# record_revf.net
KiCad netlist of a schematic drawn in EAGLE
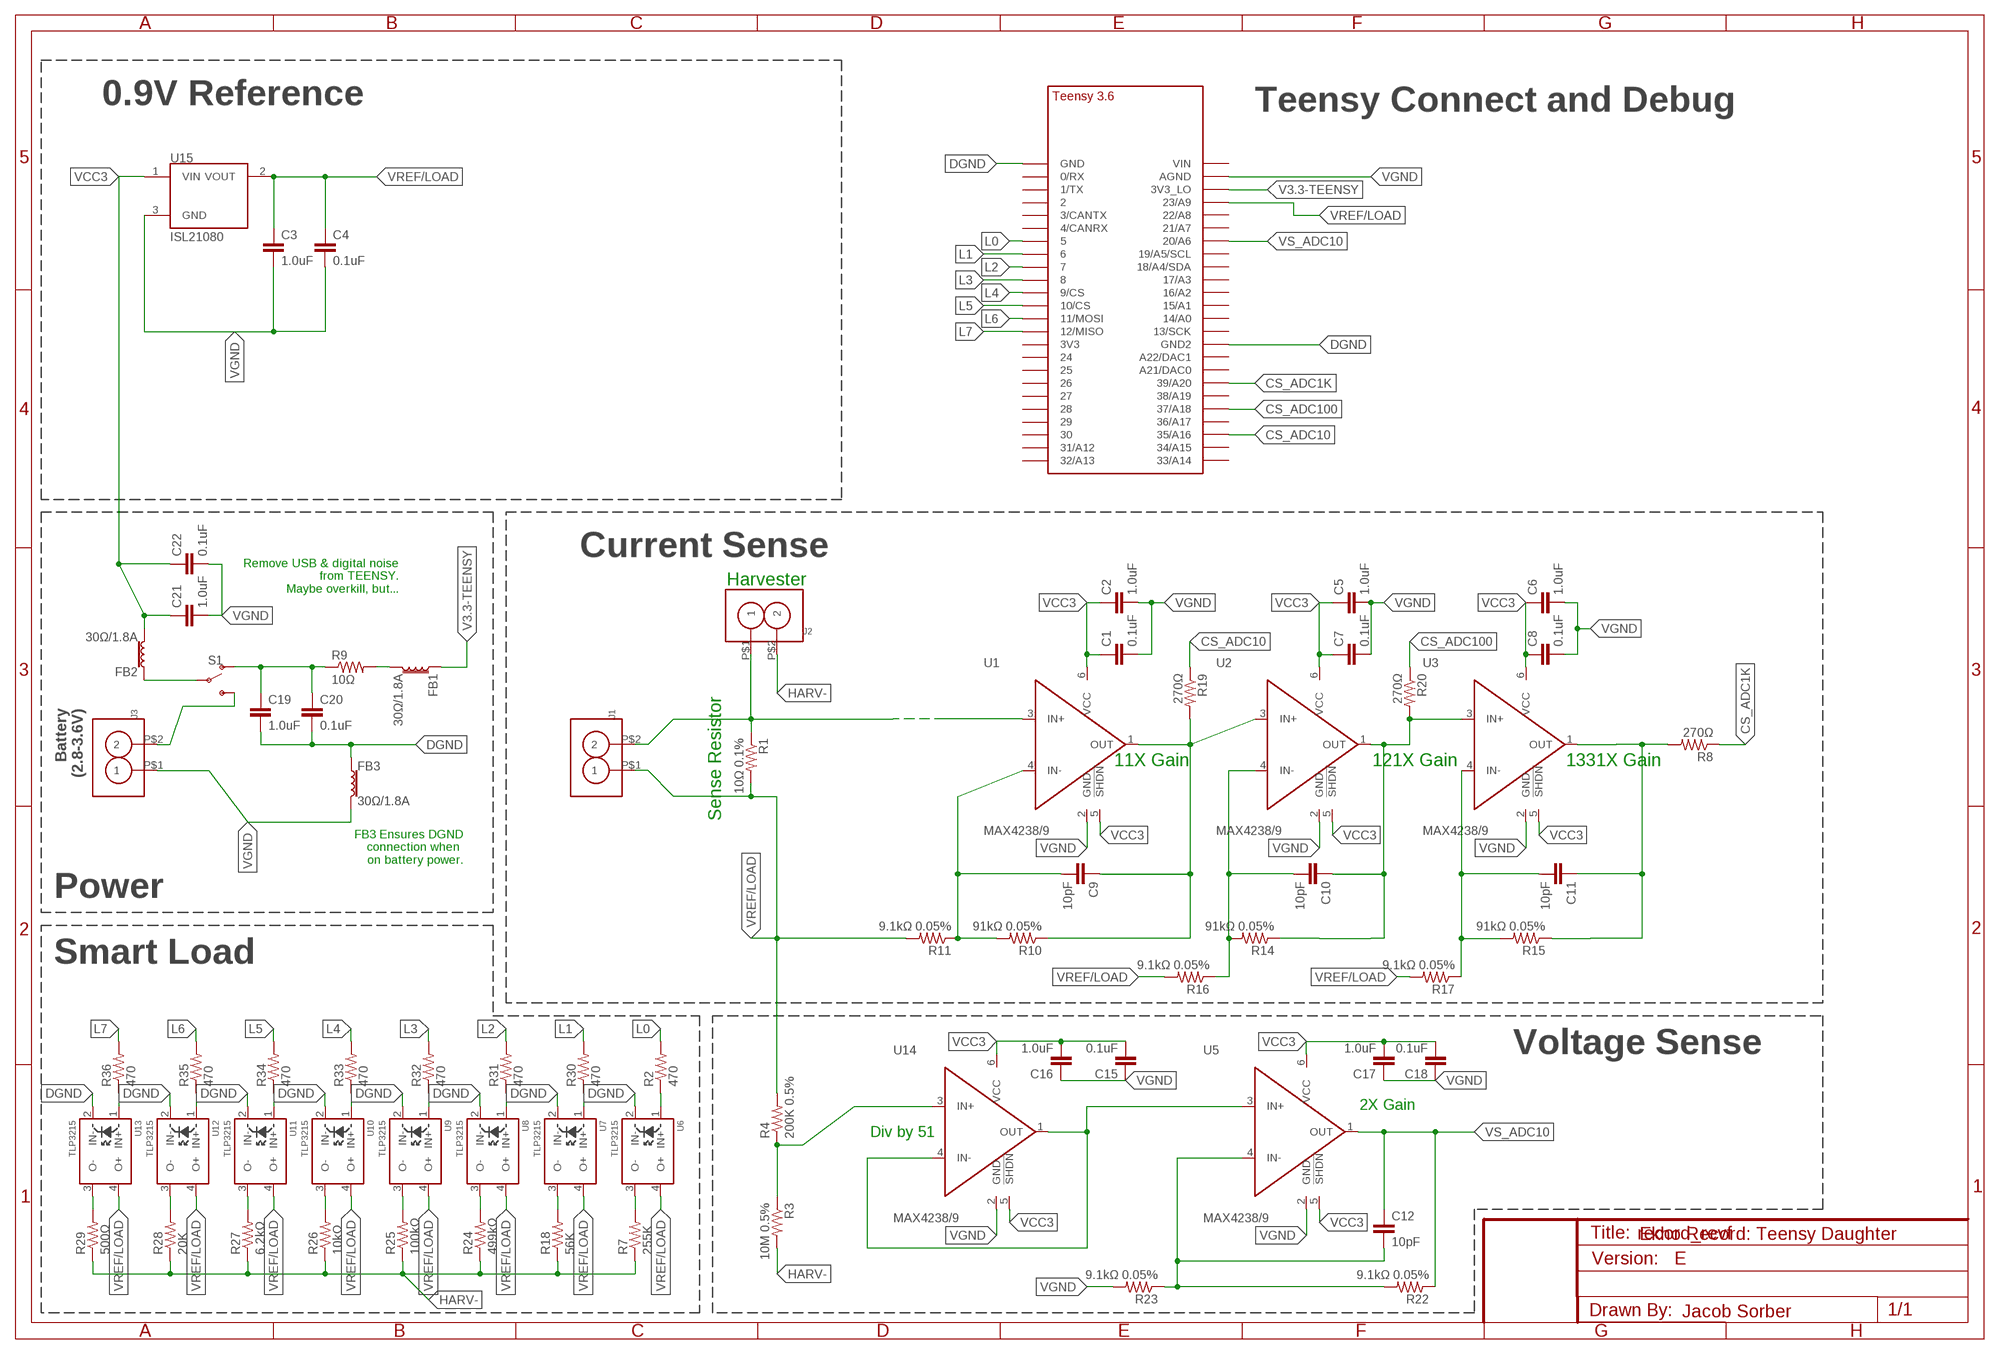
[diagram p0: schematic, sheet 1]

(export (version "E")
  (design (tool "Eeschema 10.0.6"))
  (components
    (comp (ref "C1")
      (value "0.1uF")
      (footprint "eagle-import:0603")
      (libsource (lib "eagle-import") (part "C-EU0603"))
    )
    (comp (ref "C2")
      (value "1.0uF")
      (footprint "eagle-import:0603")
      (libsource (lib "eagle-import") (part "C-EU0603"))
    )
    (comp (ref "C3")
      (value "1.0uF")
      (footprint "eagle-import:0603")
      (libsource (lib "eagle-import") (part "C-EU0603"))
    )
    (comp (ref "C4")
      (value "0.1uF")
      (footprint "eagle-import:0603")
      (libsource (lib "eagle-import") (part "C-EU0603"))
    )
    (comp (ref "C5")
      (value "1.0uF")
      (footprint "eagle-import:0603")
      (libsource (lib "eagle-import") (part "C-EU0603"))
    )
    (comp (ref "C6")
      (value "1.0uF")
      (footprint "eagle-import:0603")
      (libsource (lib "eagle-import") (part "C-EU0603"))
    )
    (comp (ref "C7")
      (value "0.1uF")
      (footprint "eagle-import:0603")
      (libsource (lib "eagle-import") (part "C-EU0603"))
    )
    (comp (ref "C8")
      (value "0.1uF")
      (footprint "eagle-import:0603")
      (libsource (lib "eagle-import") (part "C-EU0603"))
    )
    (comp (ref "C9")
      (value "10pF")
      (footprint "eagle-import:0603")
      (libsource (lib "eagle-import") (part "C-EU0603"))
    )
    (comp (ref "C10")
      (value "10pF")
      (footprint "eagle-import:0603")
      (libsource (lib "eagle-import") (part "C-EU0603"))
    )
    (comp (ref "C11")
      (value "10pF")
      (footprint "eagle-import:0603")
      (libsource (lib "eagle-import") (part "C-EU0603"))
    )
    (comp (ref "C12")
      (value "10pF")
      (footprint "eagle-import:0603")
      (libsource (lib "eagle-import") (part "C-EU0603"))
    )
    (comp (ref "C15")
      (value "0.1uF")
      (footprint "eagle-import:0603")
      (libsource (lib "eagle-import") (part "C-EU0603"))
    )
    (comp (ref "C16")
      (value "1.0uF")
      (footprint "eagle-import:0603")
      (libsource (lib "eagle-import") (part "C-EU0603"))
    )
    (comp (ref "C17")
      (value "1.0uF")
      (footprint "eagle-import:0603")
      (libsource (lib "eagle-import") (part "C-EU0603"))
    )
    (comp (ref "C18")
      (value "0.1uF")
      (footprint "eagle-import:0603")
      (libsource (lib "eagle-import") (part "C-EU0603"))
    )
    (comp (ref "C19")
      (value "1.0uF")
      (footprint "eagle-import:0603")
      (libsource (lib "eagle-import") (part "C-EU0603"))
    )
    (comp (ref "C20")
      (value "0.1uF")
      (footprint "eagle-import:0603")
      (libsource (lib "eagle-import") (part "C-EU0603"))
    )
    (comp (ref "C21")
      (value "1.0uF")
      (footprint "eagle-import:0603")
      (libsource (lib "eagle-import") (part "C-EU0603"))
    )
    (comp (ref "C22")
      (value "0.1uF")
      (footprint "eagle-import:0603")
      (libsource (lib "eagle-import") (part "C-EU0603"))
    )
    (comp (ref "FB1")
      (value "30Ω/1.8A")
      (footprint "eagle-import:0603")
      (libsource (lib "eagle-import") (part "FERRITE_BEAD-0603"))
    )
    (comp (ref "FB2")
      (value "30Ω/1.8A")
      (footprint "eagle-import:0603")
      (libsource (lib "eagle-import") (part "FERRITE_BEAD-0603"))
    )
    (comp (ref "FB3")
      (value "30Ω/1.8A")
      (footprint "eagle-import:0603")
      (libsource (lib "eagle-import") (part "FERRITE_BEAD-0603"))
    )
    (comp (ref "J1")
      (value "SCREW_CONNECTOR-2PIN'")
      (footprint "eagle-import:SCREW_CONNECTOR-2PIN-3.5MM")
      (libsource (lib "eagle-import") (part "SCREW_CONNECTOR-2PIN'"))
    )
    (comp (ref "J2")
      (value "SCREW_CONNECTOR-2PIN'")
      (footprint "eagle-import:SCREW_CONNECTOR-2PIN-3.5MM")
      (libsource (lib "eagle-import") (part "SCREW_CONNECTOR-2PIN'"))
    )
    (comp (ref "J3")
      (value "SCREW_CONNECTOR-2PIN'")
      (footprint "eagle-import:SCREW_CONNECTOR-2PIN-3.5MM")
      (libsource (lib "eagle-import") (part "SCREW_CONNECTOR-2PIN'"))
    )
    (comp (ref "R1")
      (value "10Ω 0.1%")
      (footprint "eagle-import:0805")
      (libsource (lib "eagle-import") (part "RESISTOR0805-RES"))
    )
    (comp (ref "R2")
      (value "470")
      (footprint "eagle-import:0603")
      (libsource (lib "eagle-import") (part "R-EU0603"))
    )
    (comp (ref "R3")
      (value "10M 0.5%")
      (footprint "eagle-import:0603")
      (libsource (lib "eagle-import") (part "R-EU0603"))
    )
    (comp (ref "R4")
      (value "200K 0.5%")
      (footprint "eagle-import:0603")
      (libsource (lib "eagle-import") (part "R-EU0603"))
    )
    (comp (ref "R7")
      (value "255K")
      (footprint "eagle-import:0603")
      (libsource (lib "eagle-import") (part "R-EU0603"))
    )
    (comp (ref "R8")
      (value "270Ω")
      (footprint "eagle-import:0603")
      (libsource (lib "eagle-import") (part "R-EU0603"))
    )
    (comp (ref "R9")
      (value "10Ω")
      (footprint "eagle-import:0805")
      (libsource (lib "eagle-import") (part "RESISTOR0805-RES"))
    )
    (comp (ref "R10")
      (value "91kΩ 0.05%")
      (footprint "eagle-import:0603")
      (libsource (lib "eagle-import") (part "R-EU0603"))
    )
    (comp (ref "R11")
      (value "9.1kΩ 0.05%")
      (footprint "eagle-import:0603")
      (libsource (lib "eagle-import") (part "R-EU0603"))
    )
    (comp (ref "R14")
      (value "91kΩ 0.05%")
      (footprint "eagle-import:0603")
      (libsource (lib "eagle-import") (part "R-EU0603"))
    )
    (comp (ref "R15")
      (value "91kΩ 0.05%")
      (footprint "eagle-import:0603")
      (libsource (lib "eagle-import") (part "R-EU0603"))
    )
    (comp (ref "R16")
      (value "9.1kΩ 0.05%")
      (footprint "eagle-import:0603")
      (libsource (lib "eagle-import") (part "R-EU0603"))
    )
    (comp (ref "R17")
      (value "9.1kΩ 0.05%")
      (footprint "eagle-import:0603")
      (libsource (lib "eagle-import") (part "R-EU0603"))
    )
    (comp (ref "R18")
      (value "56K")
      (footprint "eagle-import:0603")
      (libsource (lib "eagle-import") (part "R-EU0603"))
    )
    (comp (ref "R19")
      (value "270Ω")
      (footprint "eagle-import:0603")
      (libsource (lib "eagle-import") (part "R-EU0603"))
    )
    (comp (ref "R20")
      (value "270Ω")
      (footprint "eagle-import:0603")
      (libsource (lib "eagle-import") (part "R-EU0603"))
    )
    (comp (ref "R22")
      (value "9.1kΩ 0.05%")
      (footprint "eagle-import:0603")
      (libsource (lib "eagle-import") (part "R-EU0603"))
    )
    (comp (ref "R23")
      (value "9.1kΩ 0.05%")
      (footprint "eagle-import:0603")
      (libsource (lib "eagle-import") (part "R-EU0603"))
    )
    (comp (ref "R24")
      (value "499kΩ")
      (footprint "eagle-import:0603")
      (libsource (lib "eagle-import") (part "R-EU0603"))
    )
    (comp (ref "R25")
      (value "100kΩ")
      (footprint "eagle-import:0603")
      (libsource (lib "eagle-import") (part "R-EU0603"))
    )
    (comp (ref "R26")
      (value "10kΩ")
      (footprint "eagle-import:0603")
      (libsource (lib "eagle-import") (part "R-EU0603"))
    )
    (comp (ref "R27")
      (value "6.2kΩ")
      (footprint "eagle-import:0603")
      (libsource (lib "eagle-import") (part "R-EU0603"))
    )
    (comp (ref "R28")
      (value "20K")
      (footprint "eagle-import:0603")
      (libsource (lib "eagle-import") (part "R-EU0603"))
    )
    (comp (ref "R29")
      (value "500Ω")
      (footprint "eagle-import:0603")
      (libsource (lib "eagle-import") (part "R-EU0603"))
    )
    (comp (ref "R30")
      (value "470")
      (footprint "eagle-import:0603")
      (libsource (lib "eagle-import") (part "R-EU0603"))
    )
    (comp (ref "R31")
      (value "470")
      (footprint "eagle-import:0603")
      (libsource (lib "eagle-import") (part "R-EU0603"))
    )
    (comp (ref "R32")
      (value "470")
      (footprint "eagle-import:0603")
      (libsource (lib "eagle-import") (part "R-EU0603"))
    )
    (comp (ref "R33")
      (value "470")
      (footprint "eagle-import:0603")
      (libsource (lib "eagle-import") (part "R-EU0603"))
    )
    (comp (ref "R34")
      (value "470")
      (footprint "eagle-import:0603")
      (libsource (lib "eagle-import") (part "R-EU0603"))
    )
    (comp (ref "R35")
      (value "470")
      (footprint "eagle-import:0603")
      (libsource (lib "eagle-import") (part "R-EU0603"))
    )
    (comp (ref "R36")
      (value "470")
      (footprint "eagle-import:0603")
      (libsource (lib "eagle-import") (part "R-EU0603"))
    )
    (comp (ref "S1")
      (value "SWITCH-SPDT-PTH-11.6X4.0MM-KIT")
      (footprint "eagle-import:SWITCH_SPDT_PTH_11.6X4.0MM_KIT")
      (libsource (lib "eagle-import") (part "SWITCH-SPDT-PTH-11.6X4.0MM-KIT"))
    )
    (comp (ref "U$6")
      (value "TEENSY_3.5/3.6_SIDE_ONLY")
      (footprint "eagle-import:TEENSY_3.5_3.6_SIDE_ONLY")
      (libsource (lib "eagle-import") (part "TEENSY_3.5/3.6_SIDE_ONLY"))
    )
    (comp (ref "U1")
      (value "MAX4238/9")
      (footprint "eagle-import:SOT23-6")
      (libsource (lib "eagle-import") (part "MAX4238/9"))
    )
    (comp (ref "U2")
      (value "MAX4238/9")
      (footprint "eagle-import:SOT23-6")
      (libsource (lib "eagle-import") (part "MAX4238/9"))
    )
    (comp (ref "U3")
      (value "MAX4238/9")
      (footprint "eagle-import:SOT23-6")
      (libsource (lib "eagle-import") (part "MAX4238/9"))
    )
    (comp (ref "U5")
      (value "MAX4238/9")
      (footprint "eagle-import:SOT23-6")
      (libsource (lib "eagle-import") (part "MAX4238/9"))
    )
    (comp (ref "U6")
      (value "TLP3215")
      (footprint "eagle-import:TLP3215")
      (libsource (lib "eagle-import") (part "TLP3215"))
    )
    (comp (ref "U7")
      (value "TLP3215")
      (footprint "eagle-import:TLP3215")
      (libsource (lib "eagle-import") (part "TLP3215"))
    )
    (comp (ref "U8")
      (value "TLP3215")
      (footprint "eagle-import:TLP3215")
      (libsource (lib "eagle-import") (part "TLP3215"))
    )
    (comp (ref "U9")
      (value "TLP3215")
      (footprint "eagle-import:TLP3215")
      (libsource (lib "eagle-import") (part "TLP3215"))
    )
    (comp (ref "U10")
      (value "TLP3215")
      (footprint "eagle-import:TLP3215")
      (libsource (lib "eagle-import") (part "TLP3215"))
    )
    (comp (ref "U11")
      (value "TLP3215")
      (footprint "eagle-import:TLP3215")
      (libsource (lib "eagle-import") (part "TLP3215"))
    )
    (comp (ref "U12")
      (value "TLP3215")
      (footprint "eagle-import:TLP3215")
      (libsource (lib "eagle-import") (part "TLP3215"))
    )
    (comp (ref "U13")
      (value "TLP3215")
      (footprint "eagle-import:TLP3215")
      (libsource (lib "eagle-import") (part "TLP3215"))
    )
    (comp (ref "U14")
      (value "MAX4238/9")
      (footprint "eagle-import:SOT23-6")
      (libsource (lib "eagle-import") (part "MAX4238/9"))
    )
    (comp (ref "U15")
      (value "ISL21080")
      (footprint "eagle-import:SOT-23")
      (libsource (lib "eagle-import") (part "ISL21080"))
    )
  )
  (nets
    (net (code "1") (name "CS_ADC1K") (class "Default")
      (node (ref "R8") (pin "1") (pinfunction "1_1") (pintype "passive"))
      (node (ref "U$6") (pin "39/A20") (pinfunction "39/A20_39/A20") (pintype "bidirectional"))
    )
    (net (code "2") (name "CS_ADC10") (class "Default")
      (node (ref "R19") (pin "1") (pinfunction "1_1") (pintype "passive"))
      (node (ref "U$6") (pin "35/A16") (pinfunction "35/A16_35/A16") (pintype "bidirectional"))
    )
    (net (code "3") (name "CS_ADC100") (class "Default")
      (node (ref "R20") (pin "1") (pinfunction "1_1") (pintype "passive"))
      (node (ref "U$6") (pin "37/A18") (pinfunction "37/A18_37/A18") (pintype "bidirectional"))
    )
    (net (code "4") (name "DGND") (class "Default")
      (node (ref "C19") (pin "2") (pinfunction "2_2") (pintype "passive"))
      (node (ref "C20") (pin "2") (pinfunction "2_2") (pintype "passive"))
      (node (ref "FB3") (pin "1") (pinfunction "1_1") (pintype "passive"))
      (node (ref "U$6") (pin "GND") (pinfunction "GND_GND") (pintype "bidirectional"))
      (node (ref "U$6") (pin "GND2") (pinfunction "GND2_GND2") (pintype "bidirectional"))
      (node (ref "U10") (pin "2") (pinfunction "IN-_2") (pintype "bidirectional"))
      (node (ref "U11") (pin "2") (pinfunction "IN-_2") (pintype "bidirectional"))
      (node (ref "U12") (pin "2") (pinfunction "IN-_2") (pintype "bidirectional"))
      (node (ref "U13") (pin "2") (pinfunction "IN-_2") (pintype "bidirectional"))
      (node (ref "U6") (pin "2") (pinfunction "IN-_2") (pintype "bidirectional"))
      (node (ref "U7") (pin "2") (pinfunction "IN-_2") (pintype "bidirectional"))
      (node (ref "U8") (pin "2") (pinfunction "IN-_2") (pintype "bidirectional"))
      (node (ref "U9") (pin "2") (pinfunction "IN-_2") (pintype "bidirectional"))
    )
    (net (code "5") (name "HARV-") (class "Default")
      (node (ref "J2") (pin "P$2") (pinfunction "2_P$2") (pintype "bidirectional"))
      (node (ref "R18") (pin "1") (pinfunction "1_1") (pintype "passive"))
      (node (ref "R24") (pin "1") (pinfunction "1_1") (pintype "passive"))
      (node (ref "R25") (pin "1") (pinfunction "1_1") (pintype "passive"))
      (node (ref "R26") (pin "1") (pinfunction "1_1") (pintype "passive"))
      (node (ref "R27") (pin "1") (pinfunction "1_1") (pintype "passive"))
      (node (ref "R28") (pin "1") (pinfunction "1_1") (pintype "passive"))
      (node (ref "R29") (pin "1") (pinfunction "1_1") (pintype "passive"))
      (node (ref "R3") (pin "2") (pinfunction "2_2") (pintype "passive"))
      (node (ref "R7") (pin "1") (pinfunction "1_1") (pintype "passive"))
    )
    (net (code "6") (name "L0") (class "Default")
      (node (ref "R2") (pin "2") (pinfunction "2_2") (pintype "passive"))
      (node (ref "U$6") (pin "5") (pinfunction "5_5") (pintype "bidirectional"))
    )
    (net (code "7") (name "L1") (class "Default")
      (node (ref "R30") (pin "2") (pinfunction "2_2") (pintype "passive"))
      (node (ref "U$6") (pin "6") (pinfunction "6_6") (pintype "bidirectional"))
    )
    (net (code "8") (name "L2") (class "Default")
      (node (ref "R31") (pin "2") (pinfunction "2_2") (pintype "passive"))
      (node (ref "U$6") (pin "7") (pinfunction "7_7") (pintype "bidirectional"))
    )
    (net (code "9") (name "L3") (class "Default")
      (node (ref "R32") (pin "2") (pinfunction "2_2") (pintype "passive"))
      (node (ref "U$6") (pin "8") (pinfunction "8_8") (pintype "bidirectional"))
    )
    (net (code "10") (name "L4") (class "Default")
      (node (ref "R33") (pin "2") (pinfunction "2_2") (pintype "passive"))
      (node (ref "U$6") (pin "9/CS") (pinfunction "9/CS_9/CS") (pintype "bidirectional"))
    )
    (net (code "11") (name "L5") (class "Default")
      (node (ref "R34") (pin "2") (pinfunction "2_2") (pintype "passive"))
      (node (ref "U$6") (pin "10/CS") (pinfunction "10/CS_10/CS") (pintype "bidirectional"))
    )
    (net (code "12") (name "L6") (class "Default")
      (node (ref "R35") (pin "2") (pinfunction "2_2") (pintype "passive"))
      (node (ref "U$6") (pin "11/MOSI") (pinfunction "11/MOSI_11/MOSI") (pintype "bidirectional"))
    )
    (net (code "13") (name "L7") (class "Default")
      (node (ref "R36") (pin "2") (pinfunction "2_2") (pintype "passive"))
      (node (ref "U$6") (pin "12/MISO") (pinfunction "12/MISO_12/MISO") (pintype "bidirectional"))
    )
    (net (code "14") (name "Net-(FB1-Pad2)") (class "Default")
      (node (ref "FB1") (pin "2") (pinfunction "2_2") (pintype "passive"))
      (node (ref "R9") (pin "2") (pinfunction "2_2") (pintype "passive"))
    )
    (net (code "15") (name "Net-(J1-2)") (class "Default")
      (node (ref "J1") (pin "P$2") (pinfunction "2_P$2") (pintype "bidirectional"))
      (node (ref "J2") (pin "P$1") (pinfunction "1_P$1") (pintype "bidirectional"))
      (node (ref "R1") (pin "1") (pinfunction "1_1") (pintype "passive"))
      (node (ref "U1") (pin "3") (pinfunction "IN+_3") (pintype "bidirectional"))
    )
    (net (code "16") (name "Net-(J3-2)") (class "Default")
      (node (ref "J3") (pin "P$2") (pinfunction "2_P$2") (pintype "bidirectional"))
      (node (ref "S1") (pin "3") (pinfunction "S_3") (pintype "passive"))
    )
    (net (code "17") (name "Net-(S1-O)") (class "Default")
      (node (ref "C19") (pin "1") (pinfunction "1_1") (pintype "passive"))
      (node (ref "C20") (pin "1") (pinfunction "1_1") (pintype "passive"))
      (node (ref "R9") (pin "1") (pinfunction "1_1") (pintype "passive"))
      (node (ref "S1") (pin "1") (pinfunction "O_1") (pintype "passive"))
    )
    (net (code "18") (name "Net-(S1-P)") (class "Default")
      (node (ref "FB2") (pin "1") (pinfunction "1_1") (pintype "passive"))
      (node (ref "S1") (pin "2") (pinfunction "P_2") (pintype "passive"))
    )
    (net (code "19") (name "Net-(U1-IN-)") (class "Default")
      (node (ref "C9") (pin "2") (pinfunction "2_2") (pintype "passive"))
      (node (ref "R10") (pin "2") (pinfunction "2_2") (pintype "passive"))
      (node (ref "R11") (pin "1") (pinfunction "1_1") (pintype "passive"))
      (node (ref "U1") (pin "4") (pinfunction "IN-_4") (pintype "bidirectional"))
    )
    (net (code "20") (name "Net-(U1-OUT)") (class "Default")
      (node (ref "C9") (pin "1") (pinfunction "1_1") (pintype "passive"))
      (node (ref "R10") (pin "1") (pinfunction "1_1") (pintype "passive"))
      (node (ref "R19") (pin "2") (pinfunction "2_2") (pintype "passive"))
      (node (ref "U1") (pin "1") (pinfunction "OUT_1") (pintype "bidirectional"))
      (node (ref "U2") (pin "3") (pinfunction "IN+_3") (pintype "bidirectional"))
    )
    (net (code "21") (name "Net-(U2-IN-)") (class "Default")
      (node (ref "C10") (pin "2") (pinfunction "2_2") (pintype "passive"))
      (node (ref "R14") (pin "2") (pinfunction "2_2") (pintype "passive"))
      (node (ref "R16") (pin "1") (pinfunction "1_1") (pintype "passive"))
      (node (ref "U2") (pin "4") (pinfunction "IN-_4") (pintype "bidirectional"))
    )
    (net (code "22") (name "Net-(U2-OUT)") (class "Default")
      (node (ref "C10") (pin "1") (pinfunction "1_1") (pintype "passive"))
      (node (ref "R14") (pin "1") (pinfunction "1_1") (pintype "passive"))
      (node (ref "R20") (pin "2") (pinfunction "2_2") (pintype "passive"))
      (node (ref "U2") (pin "1") (pinfunction "OUT_1") (pintype "bidirectional"))
      (node (ref "U3") (pin "3") (pinfunction "IN+_3") (pintype "bidirectional"))
    )
    (net (code "23") (name "Net-(U3-IN-)") (class "Default")
      (node (ref "C11") (pin "2") (pinfunction "2_2") (pintype "passive"))
      (node (ref "R15") (pin "2") (pinfunction "2_2") (pintype "passive"))
      (node (ref "R17") (pin "1") (pinfunction "1_1") (pintype "passive"))
      (node (ref "U3") (pin "4") (pinfunction "IN-_4") (pintype "bidirectional"))
    )
    (net (code "24") (name "Net-(U3-OUT)") (class "Default")
      (node (ref "C11") (pin "1") (pinfunction "1_1") (pintype "passive"))
      (node (ref "R15") (pin "1") (pinfunction "1_1") (pintype "passive"))
      (node (ref "R8") (pin "2") (pinfunction "2_2") (pintype "passive"))
      (node (ref "U3") (pin "1") (pinfunction "OUT_1") (pintype "bidirectional"))
    )
    (net (code "25") (name "Net-(U5-IN-)") (class "Default")
      (node (ref "C12") (pin "2") (pinfunction "2_2") (pintype "passive"))
      (node (ref "R22") (pin "2") (pinfunction "2_2") (pintype "passive"))
      (node (ref "R23") (pin "1") (pinfunction "1_1") (pintype "passive"))
      (node (ref "U5") (pin "4") (pinfunction "IN-_4") (pintype "bidirectional"))
    )
    (net (code "26") (name "Net-(U6-IN+)") (class "Default")
      (node (ref "R2") (pin "1") (pinfunction "1_1") (pintype "passive"))
      (node (ref "U6") (pin "1") (pinfunction "IN+_1") (pintype "bidirectional"))
    )
    (net (code "27") (name "Net-(U6-O-)") (class "Default")
      (node (ref "R7") (pin "2") (pinfunction "2_2") (pintype "passive"))
      (node (ref "U6") (pin "3") (pinfunction "O-_3") (pintype "bidirectional"))
    )
    (net (code "28") (name "Net-(U7-IN+)") (class "Default")
      (node (ref "R30") (pin "1") (pinfunction "1_1") (pintype "passive"))
      (node (ref "U7") (pin "1") (pinfunction "IN+_1") (pintype "bidirectional"))
    )
    (net (code "29") (name "Net-(U7-O-)") (class "Default")
      (node (ref "R18") (pin "2") (pinfunction "2_2") (pintype "passive"))
      (node (ref "U7") (pin "3") (pinfunction "O-_3") (pintype "bidirectional"))
    )
    (net (code "30") (name "Net-(U8-IN+)") (class "Default")
      (node (ref "R31") (pin "1") (pinfunction "1_1") (pintype "passive"))
      (node (ref "U8") (pin "1") (pinfunction "IN+_1") (pintype "bidirectional"))
    )
    (net (code "31") (name "Net-(U8-O-)") (class "Default")
      (node (ref "R24") (pin "2") (pinfunction "2_2") (pintype "passive"))
      (node (ref "U8") (pin "3") (pinfunction "O-_3") (pintype "bidirectional"))
    )
    (net (code "32") (name "Net-(U9-IN+)") (class "Default")
      (node (ref "R32") (pin "1") (pinfunction "1_1") (pintype "passive"))
      (node (ref "U9") (pin "1") (pinfunction "IN+_1") (pintype "bidirectional"))
    )
    (net (code "33") (name "Net-(U9-O-)") (class "Default")
      (node (ref "R25") (pin "2") (pinfunction "2_2") (pintype "passive"))
      (node (ref "U9") (pin "3") (pinfunction "O-_3") (pintype "bidirectional"))
    )
    (net (code "34") (name "Net-(U10-IN+)") (class "Default")
      (node (ref "R33") (pin "1") (pinfunction "1_1") (pintype "passive"))
      (node (ref "U10") (pin "1") (pinfunction "IN+_1") (pintype "bidirectional"))
    )
    (net (code "35") (name "Net-(U10-O-)") (class "Default")
      (node (ref "R26") (pin "2") (pinfunction "2_2") (pintype "passive"))
      (node (ref "U10") (pin "3") (pinfunction "O-_3") (pintype "bidirectional"))
    )
    (net (code "36") (name "Net-(U11-IN+)") (class "Default")
      (node (ref "R34") (pin "1") (pinfunction "1_1") (pintype "passive"))
      (node (ref "U11") (pin "1") (pinfunction "IN+_1") (pintype "bidirectional"))
    )
    (net (code "37") (name "Net-(U11-O-)") (class "Default")
      (node (ref "R27") (pin "2") (pinfunction "2_2") (pintype "passive"))
      (node (ref "U11") (pin "3") (pinfunction "O-_3") (pintype "bidirectional"))
    )
    (net (code "38") (name "Net-(U12-IN+)") (class "Default")
      (node (ref "R35") (pin "1") (pinfunction "1_1") (pintype "passive"))
      (node (ref "U12") (pin "1") (pinfunction "IN+_1") (pintype "bidirectional"))
    )
    (net (code "39") (name "Net-(U12-O-)") (class "Default")
      (node (ref "R28") (pin "2") (pinfunction "2_2") (pintype "passive"))
      (node (ref "U12") (pin "3") (pinfunction "O-_3") (pintype "bidirectional"))
    )
    (net (code "40") (name "Net-(U13-IN+)") (class "Default")
      (node (ref "R36") (pin "1") (pinfunction "1_1") (pintype "passive"))
      (node (ref "U13") (pin "1") (pinfunction "IN+_1") (pintype "bidirectional"))
    )
    (net (code "41") (name "Net-(U13-O-)") (class "Default")
      (node (ref "R29") (pin "2") (pinfunction "2_2") (pintype "passive"))
      (node (ref "U13") (pin "3") (pinfunction "O-_3") (pintype "bidirectional"))
    )
    (net (code "42") (name "Net-(U14-IN+)") (class "Default")
      (node (ref "R3") (pin "1") (pinfunction "1_1") (pintype "passive"))
      (node (ref "R4") (pin "1") (pinfunction "1_1") (pintype "passive"))
      (node (ref "U14") (pin "3") (pinfunction "IN+_3") (pintype "bidirectional"))
    )
    (net (code "43") (name "Net-(U14-IN-)") (class "Default")
      (node (ref "U14") (pin "1") (pinfunction "OUT_1") (pintype "bidirectional"))
      (node (ref "U14") (pin "4") (pinfunction "IN-_4") (pintype "bidirectional"))
      (node (ref "U5") (pin "3") (pinfunction "IN+_3") (pintype "bidirectional"))
    )
    (net (code "44") (name "V3.3-TEENSY") (class "Default")
      (node (ref "FB1") (pin "1") (pinfunction "1_1") (pintype "passive"))
      (node (ref "U$6") (pin "3V3_LO") (pinfunction "3V3_LO_3V3_LO") (pintype "bidirectional"))
    )
    (net (code "45") (name "VCC3") (class "Default")
      (node (ref "C1") (pin "1") (pinfunction "1_1") (pintype "passive"))
      (node (ref "C15") (pin "2") (pinfunction "2_2") (pintype "passive"))
      (node (ref "C16") (pin "2") (pinfunction "2_2") (pintype "passive"))
      (node (ref "C17") (pin "2") (pinfunction "2_2") (pintype "passive"))
      (node (ref "C18") (pin "2") (pinfunction "2_2") (pintype "passive"))
      (node (ref "C2") (pin "1") (pinfunction "1_1") (pintype "passive"))
      (node (ref "C21") (pin "1") (pinfunction "1_1") (pintype "passive"))
      (node (ref "C22") (pin "1") (pinfunction "1_1") (pintype "passive"))
      (node (ref "C5") (pin "1") (pinfunction "1_1") (pintype "passive"))
      (node (ref "C6") (pin "1") (pinfunction "1_1") (pintype "passive"))
      (node (ref "C7") (pin "1") (pinfunction "1_1") (pintype "passive"))
      (node (ref "C8") (pin "1") (pinfunction "1_1") (pintype "passive"))
      (node (ref "FB2") (pin "2") (pinfunction "2_2") (pintype "passive"))
      (node (ref "U1") (pin "5") (pinfunction "~{SHDN}_5") (pintype "bidirectional"))
      (node (ref "U1") (pin "6") (pinfunction "VCC_6") (pintype "bidirectional"))
      (node (ref "U14") (pin "5") (pinfunction "~{SHDN}_5") (pintype "bidirectional"))
      (node (ref "U14") (pin "6") (pinfunction "VCC_6") (pintype "bidirectional"))
      (node (ref "U15") (pin "1") (pinfunction "VIN_1") (pintype "bidirectional"))
      (node (ref "U2") (pin "5") (pinfunction "~{SHDN}_5") (pintype "bidirectional"))
      (node (ref "U2") (pin "6") (pinfunction "VCC_6") (pintype "bidirectional"))
      (node (ref "U3") (pin "5") (pinfunction "~{SHDN}_5") (pintype "bidirectional"))
      (node (ref "U3") (pin "6") (pinfunction "VCC_6") (pintype "bidirectional"))
      (node (ref "U5") (pin "5") (pinfunction "~{SHDN}_5") (pintype "bidirectional"))
      (node (ref "U5") (pin "6") (pinfunction "VCC_6") (pintype "bidirectional"))
    )
    (net (code "46") (name "VGND") (class "Default")
      (node (ref "C1") (pin "2") (pinfunction "2_2") (pintype "passive"))
      (node (ref "C15") (pin "1") (pinfunction "1_1") (pintype "passive"))
      (node (ref "C16") (pin "1") (pinfunction "1_1") (pintype "passive"))
      (node (ref "C17") (pin "1") (pinfunction "1_1") (pintype "passive"))
      (node (ref "C18") (pin "1") (pinfunction "1_1") (pintype "passive"))
      (node (ref "C2") (pin "2") (pinfunction "2_2") (pintype "passive"))
      (node (ref "C21") (pin "2") (pinfunction "2_2") (pintype "passive"))
      (node (ref "C22") (pin "2") (pinfunction "2_2") (pintype "passive"))
      (node (ref "C3") (pin "2") (pinfunction "2_2") (pintype "passive"))
      (node (ref "C4") (pin "2") (pinfunction "2_2") (pintype "passive"))
      (node (ref "C5") (pin "2") (pinfunction "2_2") (pintype "passive"))
      (node (ref "C6") (pin "2") (pinfunction "2_2") (pintype "passive"))
      (node (ref "C7") (pin "2") (pinfunction "2_2") (pintype "passive"))
      (node (ref "C8") (pin "2") (pinfunction "2_2") (pintype "passive"))
      (node (ref "FB3") (pin "2") (pinfunction "2_2") (pintype "passive"))
      (node (ref "J3") (pin "P$1") (pinfunction "1_P$1") (pintype "bidirectional"))
      (node (ref "R23") (pin "2") (pinfunction "2_2") (pintype "passive"))
      (node (ref "U$6") (pin "AGND") (pinfunction "AGND_AGND") (pintype "bidirectional"))
      (node (ref "U1") (pin "2") (pinfunction "GND_2") (pintype "bidirectional"))
      (node (ref "U14") (pin "2") (pinfunction "GND_2") (pintype "bidirectional"))
      (node (ref "U15") (pin "3") (pinfunction "GND_3") (pintype "bidirectional"))
      (node (ref "U2") (pin "2") (pinfunction "GND_2") (pintype "bidirectional"))
      (node (ref "U3") (pin "2") (pinfunction "GND_2") (pintype "bidirectional"))
      (node (ref "U5") (pin "2") (pinfunction "GND_2") (pintype "bidirectional"))
    )
    (net (code "47") (name "VREF{slash}LOAD") (class "Default")
      (node (ref "C3") (pin "1") (pinfunction "1_1") (pintype "passive"))
      (node (ref "C4") (pin "1") (pinfunction "1_1") (pintype "passive"))
      (node (ref "J1") (pin "P$1") (pinfunction "1_P$1") (pintype "bidirectional"))
      (node (ref "R1") (pin "2") (pinfunction "2_2") (pintype "passive"))
      (node (ref "R11") (pin "2") (pinfunction "2_2") (pintype "passive"))
      (node (ref "R16") (pin "2") (pinfunction "2_2") (pintype "passive"))
      (node (ref "R17") (pin "2") (pinfunction "2_2") (pintype "passive"))
      (node (ref "R4") (pin "2") (pinfunction "2_2") (pintype "passive"))
      (node (ref "U$6") (pin "23/A9") (pinfunction "23/A9_23/A9") (pintype "bidirectional"))
      (node (ref "U10") (pin "4") (pinfunction "O+_4") (pintype "bidirectional"))
      (node (ref "U11") (pin "4") (pinfunction "O+_4") (pintype "bidirectional"))
      (node (ref "U12") (pin "4") (pinfunction "O+_4") (pintype "bidirectional"))
      (node (ref "U13") (pin "4") (pinfunction "O+_4") (pintype "bidirectional"))
      (node (ref "U15") (pin "2") (pinfunction "VOUT_2") (pintype "bidirectional"))
      (node (ref "U6") (pin "4") (pinfunction "O+_4") (pintype "bidirectional"))
      (node (ref "U7") (pin "4") (pinfunction "O+_4") (pintype "bidirectional"))
      (node (ref "U8") (pin "4") (pinfunction "O+_4") (pintype "bidirectional"))
      (node (ref "U9") (pin "4") (pinfunction "O+_4") (pintype "bidirectional"))
    )
    (net (code "48") (name "VS_ADC10") (class "Default")
      (node (ref "C12") (pin "1") (pinfunction "1_1") (pintype "passive"))
      (node (ref "R22") (pin "1") (pinfunction "1_1") (pintype "passive"))
      (node (ref "U$6") (pin "20/A6") (pinfunction "20/A6_20/A6") (pintype "bidirectional"))
      (node (ref "U5") (pin "1") (pinfunction "OUT_1") (pintype "bidirectional"))
    )
    (net (code "49") (name "unconnected-(U$6-A21{slash}DAC0-Pad21{slash}DAC0)") (class "Default")
      (node (ref "U$6") (pin "21/DAC0") (pinfunction "A21/DAC0_21/DAC0") (pintype "bidirectional"))
    )
    (net (code "50") (name "unconnected-(U$6-Pad0{slash}RX)") (class "Default")
      (node (ref "U$6") (pin "0/RX") (pinfunction "0/RX_0/RX") (pintype "bidirectional"))
    )
    (net (code "51") (name "unconnected-(U$6-Pad1{slash}TX)") (class "Default")
      (node (ref "U$6") (pin "1/TX") (pinfunction "1/TX_1/TX") (pintype "bidirectional"))
    )
    (net (code "52") (name "unconnected-(U$6-Pad2)") (class "Default")
      (node (ref "U$6") (pin "2") (pinfunction "2_2") (pintype "bidirectional"))
    )
    (net (code "53") (name "unconnected-(U$6-Pad3V3)") (class "Default")
      (node (ref "U$6") (pin "3V3") (pinfunction "3V3_3V3") (pintype "bidirectional"))
    )
    (net (code "54") (name "unconnected-(U$6-Pad3{slash}CANTX)") (class "Default")
      (node (ref "U$6") (pin "3/CANTX") (pinfunction "3/CANTX_3/CANTX") (pintype "bidirectional"))
    )
    (net (code "55") (name "unconnected-(U$6-Pad4{slash}CANRX)") (class "Default")
      (node (ref "U$6") (pin "4/CANRX") (pinfunction "4/CANRX_4/CANRX") (pintype "bidirectional"))
    )
    (net (code "56") (name "unconnected-(U$6-Pad13{slash}SCK)") (class "Default")
      (node (ref "U$6") (pin "13/SCK") (pinfunction "13/SCK_13/SCK") (pintype "bidirectional"))
    )
    (net (code "57") (name "unconnected-(U$6-Pad14{slash}A0)") (class "Default")
      (node (ref "U$6") (pin "14/A0") (pinfunction "14/A0_14/A0") (pintype "bidirectional"))
    )
    (net (code "58") (name "unconnected-(U$6-Pad15{slash}A1)") (class "Default")
      (node (ref "U$6") (pin "15/A1") (pinfunction "15/A1_15/A1") (pintype "bidirectional"))
    )
    (net (code "59") (name "unconnected-(U$6-Pad16{slash}A2)") (class "Default")
      (node (ref "U$6") (pin "16/A2") (pinfunction "16/A2_16/A2") (pintype "bidirectional"))
    )
    (net (code "60") (name "unconnected-(U$6-Pad17{slash}A3)") (class "Default")
      (node (ref "U$6") (pin "17/A3") (pinfunction "17/A3_17/A3") (pintype "bidirectional"))
    )
    (net (code "61") (name "unconnected-(U$6-Pad18{slash}A4{slash}SDA)") (class "Default")
      (node (ref "U$6") (pin "18/A4/SDA") (pinfunction "18/A4/SDA_18/A4/SDA") (pintype "bidirectional"))
    )
    (net (code "62") (name "unconnected-(U$6-Pad19{slash}A5{slash}SCL)") (class "Default")
      (node (ref "U$6") (pin "19/A5/SCL") (pinfunction "19/A5/SCL_19/A5/SCL") (pintype "bidirectional"))
    )
    (net (code "63") (name "unconnected-(U$6-Pad21{slash}A7)") (class "Default")
      (node (ref "U$6") (pin "21/A7") (pinfunction "21/A7_21/A7") (pintype "bidirectional"))
    )
    (net (code "64") (name "unconnected-(U$6-Pad22{slash}A8)") (class "Default")
      (node (ref "U$6") (pin "22/A8") (pinfunction "22/A8_22/A8") (pintype "bidirectional"))
    )
    (net (code "65") (name "unconnected-(U$6-Pad24)") (class "Default")
      (node (ref "U$6") (pin "24") (pinfunction "24_24") (pintype "bidirectional"))
    )
    (net (code "66") (name "unconnected-(U$6-Pad25)") (class "Default")
      (node (ref "U$6") (pin "25") (pinfunction "25_25") (pintype "bidirectional"))
    )
    (net (code "67") (name "unconnected-(U$6-Pad26)") (class "Default")
      (node (ref "U$6") (pin "26") (pinfunction "26_26") (pintype "bidirectional"))
    )
    (net (code "68") (name "unconnected-(U$6-Pad27)") (class "Default")
      (node (ref "U$6") (pin "27") (pinfunction "27_27") (pintype "bidirectional"))
    )
    (net (code "69") (name "unconnected-(U$6-Pad28)") (class "Default")
      (node (ref "U$6") (pin "28") (pinfunction "28_28") (pintype "bidirectional"))
    )
    (net (code "70") (name "unconnected-(U$6-Pad29)") (class "Default")
      (node (ref "U$6") (pin "29") (pinfunction "29_29") (pintype "bidirectional"))
    )
    (net (code "71") (name "unconnected-(U$6-Pad30)") (class "Default")
      (node (ref "U$6") (pin "30") (pinfunction "30_30") (pintype "bidirectional"))
    )
    (net (code "72") (name "unconnected-(U$6-Pad31{slash}A12)") (class "Default")
      (node (ref "U$6") (pin "31/A12") (pinfunction "31/A12_31/A12") (pintype "bidirectional"))
    )
    (net (code "73") (name "unconnected-(U$6-Pad32{slash}A13)") (class "Default")
      (node (ref "U$6") (pin "32/A13") (pinfunction "32/A13_32/A13") (pintype "bidirectional"))
    )
    (net (code "74") (name "unconnected-(U$6-Pad33{slash}A14)") (class "Default")
      (node (ref "U$6") (pin "33/A14") (pinfunction "33/A14_33/A14") (pintype "bidirectional"))
    )
    (net (code "75") (name "unconnected-(U$6-Pad34{slash}A15)") (class "Default")
      (node (ref "U$6") (pin "34/A15") (pinfunction "34/A15_34/A15") (pintype "bidirectional"))
    )
    (net (code "76") (name "unconnected-(U$6-Pad36{slash}A17)") (class "Default")
      (node (ref "U$6") (pin "36/A17") (pinfunction "36/A17_36/A17") (pintype "bidirectional"))
    )
    (net (code "77") (name "unconnected-(U$6-Pad38{slash}A19)") (class "Default")
      (node (ref "U$6") (pin "38/A19") (pinfunction "38/A19_38/A19") (pintype "bidirectional"))
    )
    (net (code "78") (name "unconnected-(U$6-PadA22{slash}DAC1)") (class "Default")
      (node (ref "U$6") (pin "A22/DAC1") (pinfunction "A22/DAC1_A22/DAC1") (pintype "bidirectional"))
    )
    (net (code "79") (name "unconnected-(U$6-PadVIN)") (class "Default")
      (node (ref "U$6") (pin "VIN") (pinfunction "VIN_VIN") (pintype "bidirectional"))
    )
  )
)
